# PFOP.net
KiCad netlist of a schematic drawn in EAGLE
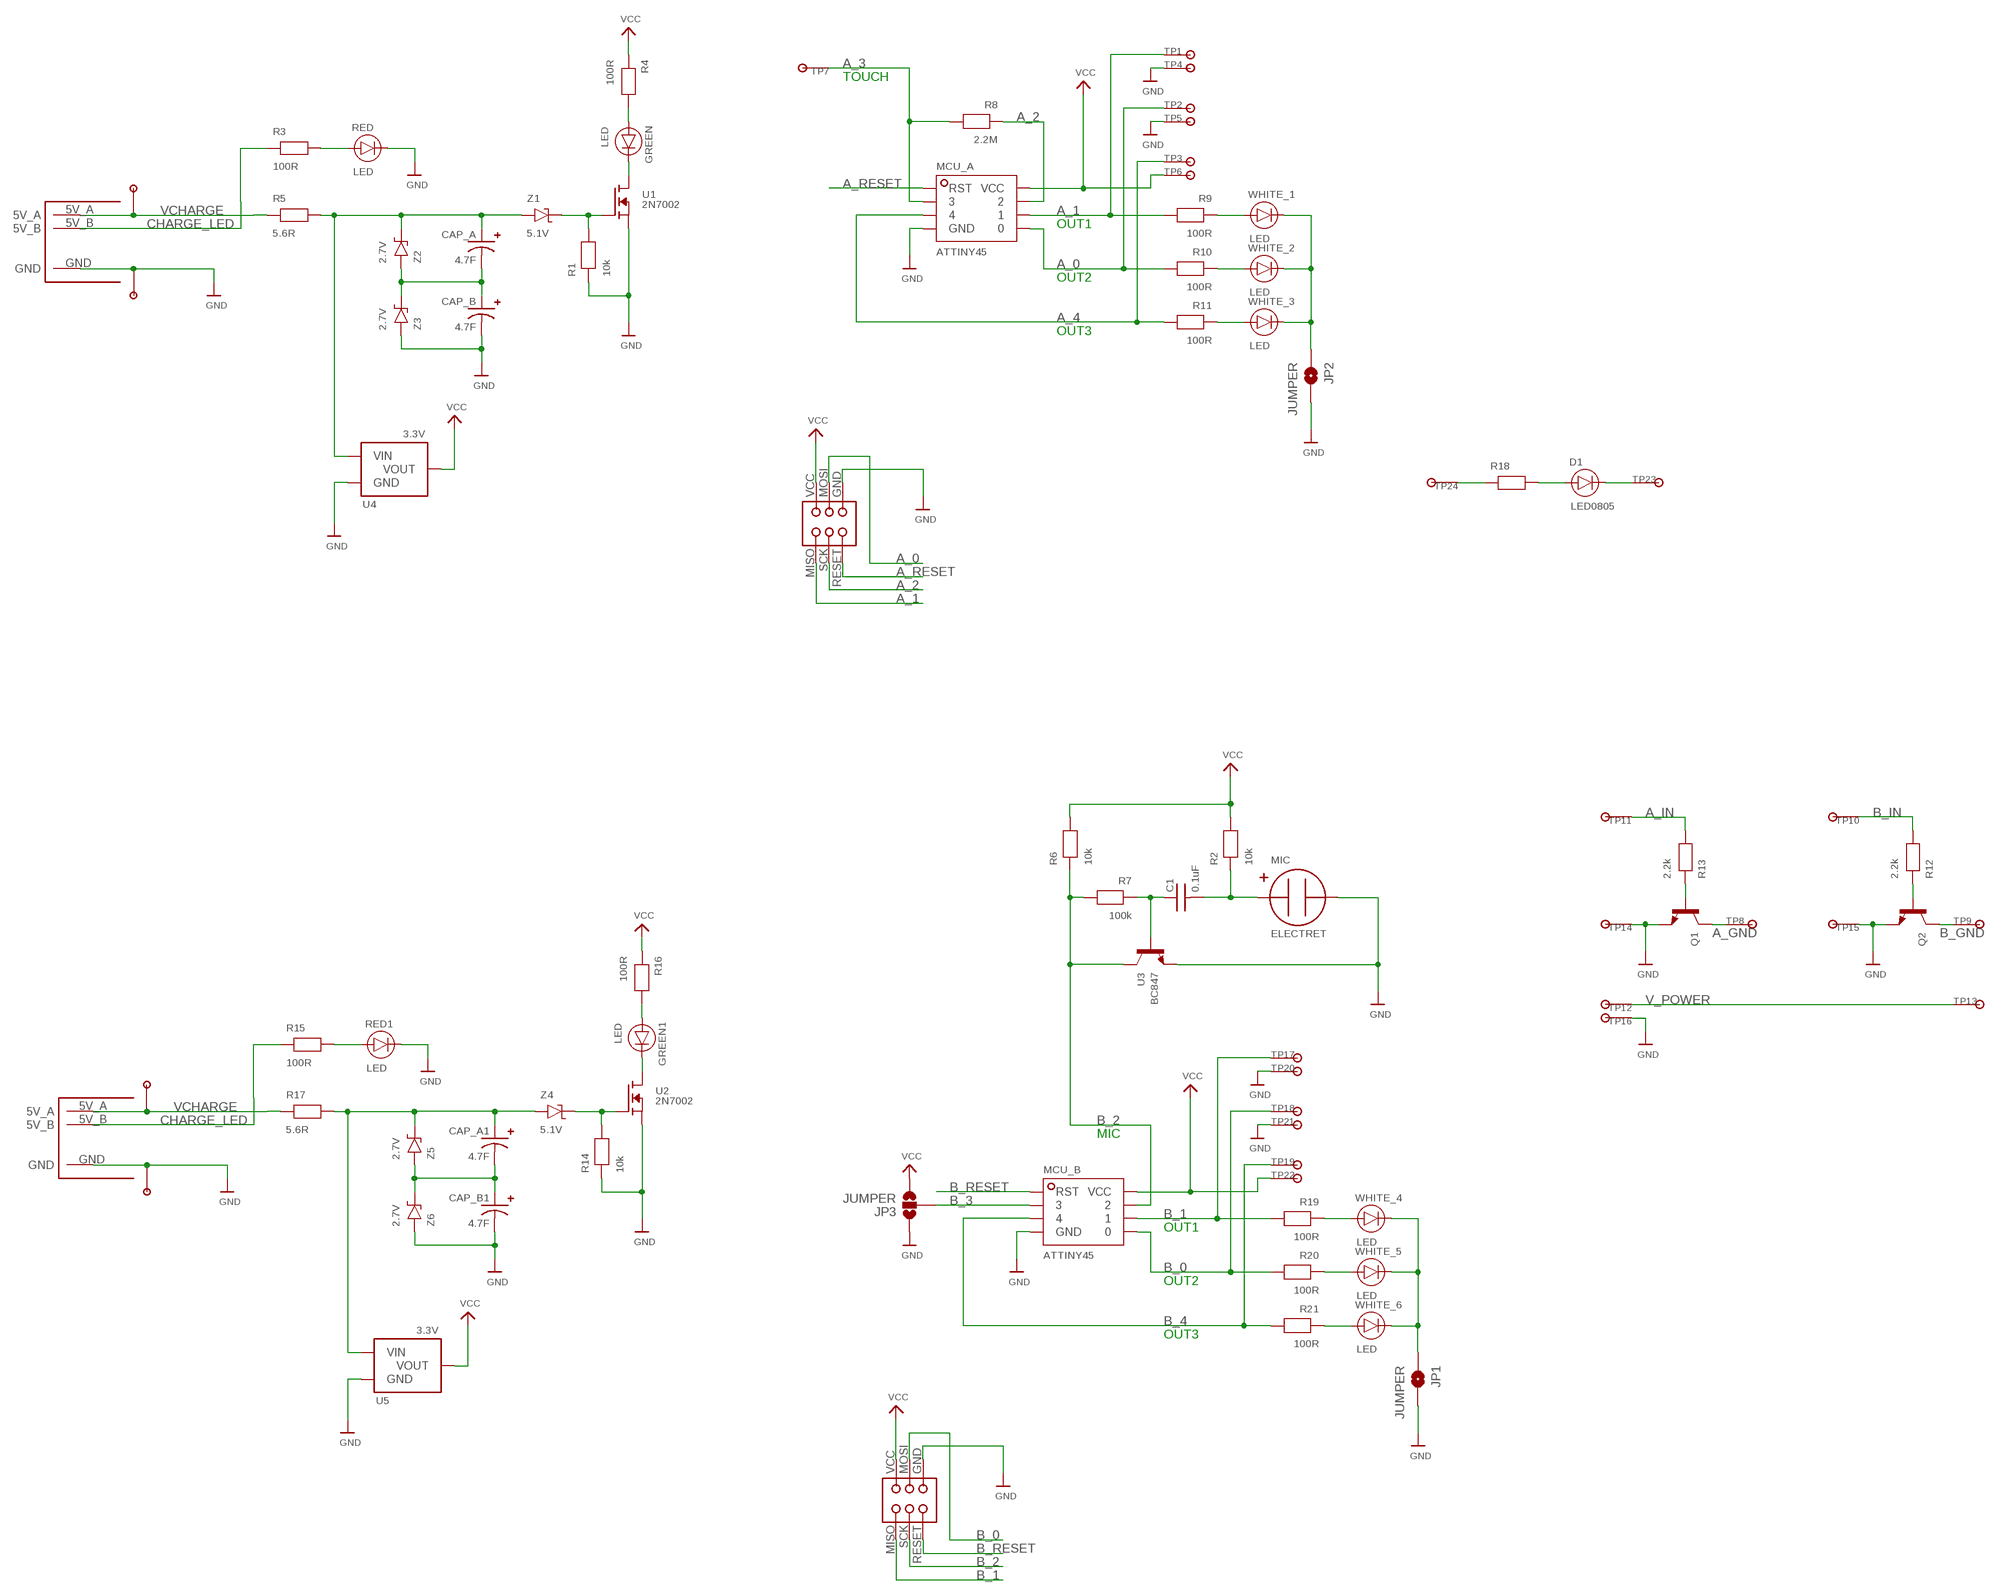
[diagram p0: schematic, sheet 1]

(export (version "E")
  (design (tool "Eeschema 10.0.6"))
  (components
    (comp (ref "C1")
      (value "0.1uF")
      (footprint "eagle-import:0805")
      (libsource (lib "eagle-import") (part "CAP"))
    )
    (comp (ref "CAP_A")
      (value "4.7F")
      (footprint "eagle-import:SUPERCAP_2.7V-4.7F")
      (libsource (lib "eagle-import") (part "SUPERCAP"))
    )
    (comp (ref "CAP_A1")
      (value "4.7F")
      (footprint "eagle-import:SUPERCAP_2.7V-4.7F")
      (libsource (lib "eagle-import") (part "SUPERCAP"))
    )
    (comp (ref "CAP_B")
      (value "4.7F")
      (footprint "eagle-import:SUPERCAP_2.7V-4.7F")
      (libsource (lib "eagle-import") (part "SUPERCAP"))
    )
    (comp (ref "CAP_B1")
      (value "4.7F")
      (footprint "eagle-import:SUPERCAP_2.7V-4.7F")
      (libsource (lib "eagle-import") (part "SUPERCAP"))
    )
    (comp (ref "D1")
      (value "LED0805")
      (footprint "eagle-import:0805_LED")
      (libsource (lib "eagle-import") (part "LED0805"))
    )
    (comp (ref "GREEN")
      (value "LED")
      (footprint "eagle-import:0805_LED")
      (libsource (lib "eagle-import") (part "LED0805"))
    )
    (comp (ref "GREEN1")
      (value "LED")
      (footprint "eagle-import:0805_LED")
      (libsource (lib "eagle-import") (part "LED0805"))
    )
    (comp (ref "J1")
      (value "ISP_HEADER")
      (footprint "eagle-import:ISP_HEADER")
      (libsource (lib "eagle-import") (part "ISP_HEADER"))
    )
    (comp (ref "J2")
      (value "ISP_HEADER")
      (footprint "eagle-import:ISP_HEADER")
      (libsource (lib "eagle-import") (part "ISP_HEADER"))
    )
    (comp (ref "JP1")
      (value "JUMPER")
      (footprint "eagle-import:SMT-JUMPER_2_NO_NO-SILK")
      (libsource (lib "eagle-import") (part "JUMPER-SMT_2_NO_NO-SILK"))
    )
    (comp (ref "JP2")
      (value "JUMPER")
      (footprint "eagle-import:SMT-JUMPER_2_NO_NO-SILK")
      (libsource (lib "eagle-import") (part "JUMPER-SMT_2_NO_NO-SILK"))
    )
    (comp (ref "JP3")
      (value "JUMPER")
      (footprint "eagle-import:SMT-JUMPER_3_NO_NO-SILK")
      (libsource (lib "eagle-import") (part "JUMPER-SMT_3_NO_NO-SILK"))
    )
    (comp (ref "MCU_A")
      (value "ATTINY45")
      (footprint "eagle-import:TSSOP-8")
      (libsource (lib "eagle-import") (part "ATTINY45"))
    )
    (comp (ref "MCU_B")
      (value "ATTINY45")
      (footprint "eagle-import:TSSOP-8")
      (libsource (lib "eagle-import") (part "ATTINY45"))
    )
    (comp (ref "MIC")
      (value "ELECTRET")
      (footprint "eagle-import:ELECTRET_4.5MM")
      (libsource (lib "eagle-import") (part "ELECTRET"))
    )
    (comp (ref "Q1")
      (value "POWER_TRANSISTOR")
      (footprint "eagle-import:POWER_TRANSISTOR")
      (libsource (lib "eagle-import") (part "POWER_TRANSISTOR"))
    )
    (comp (ref "Q2")
      (value "POWER_TRANSISTOR")
      (footprint "eagle-import:POWER_TRANSISTOR")
      (libsource (lib "eagle-import") (part "POWER_TRANSISTOR"))
    )
    (comp (ref "R1")
      (value "10k")
      (footprint "eagle-import:0805")
      (libsource (lib "eagle-import") (part "RESISTOR"))
    )
    (comp (ref "R2")
      (value "10k")
      (footprint "eagle-import:0805")
      (libsource (lib "eagle-import") (part "RESISTOR"))
    )
    (comp (ref "R3")
      (value "100R")
      (footprint "eagle-import:0805")
      (libsource (lib "eagle-import") (part "RESISTOR"))
    )
    (comp (ref "R4")
      (value "100R")
      (footprint "eagle-import:0805")
      (libsource (lib "eagle-import") (part "RESISTOR"))
    )
    (comp (ref "R5")
      (value "5.6R")
      (footprint "eagle-import:2512")
      (libsource (lib "eagle-import") (part "RESISTORPOWER"))
    )
    (comp (ref "R6")
      (value "10k")
      (footprint "eagle-import:0805")
      (libsource (lib "eagle-import") (part "RESISTOR"))
    )
    (comp (ref "R7")
      (value "100k")
      (footprint "eagle-import:0805")
      (libsource (lib "eagle-import") (part "RESISTOR"))
    )
    (comp (ref "R8")
      (value "2.2M")
      (footprint "eagle-import:0805")
      (libsource (lib "eagle-import") (part "RESISTOR"))
    )
    (comp (ref "R9")
      (value "100R")
      (footprint "eagle-import:0805")
      (libsource (lib "eagle-import") (part "RESISTOR"))
    )
    (comp (ref "R10")
      (value "100R")
      (footprint "eagle-import:0805")
      (libsource (lib "eagle-import") (part "RESISTOR"))
    )
    (comp (ref "R11")
      (value "100R")
      (footprint "eagle-import:0805")
      (libsource (lib "eagle-import") (part "RESISTOR"))
    )
    (comp (ref "R12")
      (value "2.2k")
      (footprint "eagle-import:0805")
      (libsource (lib "eagle-import") (part "RESISTOR"))
    )
    (comp (ref "R13")
      (value "2.2k")
      (footprint "eagle-import:0805")
      (libsource (lib "eagle-import") (part "RESISTOR"))
    )
    (comp (ref "R14")
      (value "10k")
      (footprint "eagle-import:0805")
      (libsource (lib "eagle-import") (part "RESISTOR"))
    )
    (comp (ref "R15")
      (value "100R")
      (footprint "eagle-import:0805")
      (libsource (lib "eagle-import") (part "RESISTOR"))
    )
    (comp (ref "R16")
      (value "100R")
      (footprint "eagle-import:0805")
      (libsource (lib "eagle-import") (part "RESISTOR"))
    )
    (comp (ref "R17")
      (value "5.6R")
      (footprint "eagle-import:2512")
      (libsource (lib "eagle-import") (part "RESISTORPOWER"))
    )
    (comp (ref "R18")
      (value "RESISTOR")
      (footprint "eagle-import:0805")
      (libsource (lib "eagle-import") (part "RESISTOR"))
    )
    (comp (ref "R19")
      (value "100R")
      (footprint "eagle-import:0805")
      (libsource (lib "eagle-import") (part "RESISTOR"))
    )
    (comp (ref "R20")
      (value "100R")
      (footprint "eagle-import:0805")
      (libsource (lib "eagle-import") (part "RESISTOR"))
    )
    (comp (ref "R21")
      (value "100R")
      (footprint "eagle-import:0805")
      (libsource (lib "eagle-import") (part "RESISTOR"))
    )
    (comp (ref "RED")
      (value "LED")
      (footprint "eagle-import:0805_LED")
      (libsource (lib "eagle-import") (part "LED0805"))
    )
    (comp (ref "RED1")
      (value "LED")
      (footprint "eagle-import:0805_LED")
      (libsource (lib "eagle-import") (part "LED0805"))
    )
    (comp (ref "TP1")
      (value "SEWTAPBIG")
      (footprint "eagle-import:BIGTAP")
      (libsource (lib "eagle-import") (part "SEWTAPBIG"))
    )
    (comp (ref "TP2")
      (value "SEWTAPBIG")
      (footprint "eagle-import:BIGTAP")
      (libsource (lib "eagle-import") (part "SEWTAPBIG"))
    )
    (comp (ref "TP3")
      (value "SEWTAPBIG")
      (footprint "eagle-import:BIGTAP")
      (libsource (lib "eagle-import") (part "SEWTAPBIG"))
    )
    (comp (ref "TP4")
      (value "SEWTAPBIG")
      (footprint "eagle-import:BIGTAP")
      (libsource (lib "eagle-import") (part "SEWTAPBIG"))
    )
    (comp (ref "TP5")
      (value "SEWTAPBIG")
      (footprint "eagle-import:BIGTAP")
      (libsource (lib "eagle-import") (part "SEWTAPBIG"))
    )
    (comp (ref "TP6")
      (value "SEWTAPBIG")
      (footprint "eagle-import:BIGTAP")
      (libsource (lib "eagle-import") (part "SEWTAPBIG"))
    )
    (comp (ref "TP7")
      (value "SEWTAP")
      (footprint "eagle-import:BIGTAP_TOUCH")
      (libsource (lib "eagle-import") (part "SEWTAP"))
    )
    (comp (ref "TP8")
      (value "SEWTAPBIG")
      (footprint "eagle-import:BIGTAP")
      (libsource (lib "eagle-import") (part "SEWTAPBIG"))
    )
    (comp (ref "TP9")
      (value "SEWTAPBIG")
      (footprint "eagle-import:BIGTAP")
      (libsource (lib "eagle-import") (part "SEWTAPBIG"))
    )
    (comp (ref "TP10")
      (value "SEWTAPBIG")
      (footprint "eagle-import:BIGTAP")
      (libsource (lib "eagle-import") (part "SEWTAPBIG"))
    )
    (comp (ref "TP11")
      (value "SEWTAPBIG")
      (footprint "eagle-import:BIGTAP")
      (libsource (lib "eagle-import") (part "SEWTAPBIG"))
    )
    (comp (ref "TP12")
      (value "SEWTAPBIG")
      (footprint "eagle-import:BIGTAP")
      (libsource (lib "eagle-import") (part "SEWTAPBIG"))
    )
    (comp (ref "TP13")
      (value "SEWTAPBIG")
      (footprint "eagle-import:BIGTAP")
      (libsource (lib "eagle-import") (part "SEWTAPBIG"))
    )
    (comp (ref "TP14")
      (value "SEWTAPBIG")
      (footprint "eagle-import:BIGTAP")
      (libsource (lib "eagle-import") (part "SEWTAPBIG"))
    )
    (comp (ref "TP15")
      (value "SEWTAPBIG")
      (footprint "eagle-import:BIGTAP")
      (libsource (lib "eagle-import") (part "SEWTAPBIG"))
    )
    (comp (ref "TP16")
      (value "SEWTAPBIG")
      (footprint "eagle-import:BIGTAP")
      (libsource (lib "eagle-import") (part "SEWTAPBIG"))
    )
    (comp (ref "TP17")
      (value "SEWTAPBIG")
      (footprint "eagle-import:BIGTAP")
      (libsource (lib "eagle-import") (part "SEWTAPBIG"))
    )
    (comp (ref "TP18")
      (value "SEWTAPBIG")
      (footprint "eagle-import:BIGTAP")
      (libsource (lib "eagle-import") (part "SEWTAPBIG"))
    )
    (comp (ref "TP19")
      (value "SEWTAPBIG")
      (footprint "eagle-import:BIGTAP")
      (libsource (lib "eagle-import") (part "SEWTAPBIG"))
    )
    (comp (ref "TP20")
      (value "SEWTAPBIG")
      (footprint "eagle-import:BIGTAP")
      (libsource (lib "eagle-import") (part "SEWTAPBIG"))
    )
    (comp (ref "TP21")
      (value "SEWTAPBIG")
      (footprint "eagle-import:BIGTAP")
      (libsource (lib "eagle-import") (part "SEWTAPBIG"))
    )
    (comp (ref "TP22")
      (value "SEWTAPBIG")
      (footprint "eagle-import:BIGTAP")
      (libsource (lib "eagle-import") (part "SEWTAPBIG"))
    )
    (comp (ref "TP23")
      (value "SEWTAPSEQUIN")
      (footprint "eagle-import:SEQUIN_TERMINAL")
      (libsource (lib "eagle-import") (part "SEWTAPSEQUIN"))
    )
    (comp (ref "TP24")
      (value "SEWTAPSEQUIN")
      (footprint "eagle-import:SEQUIN_TERMINAL")
      (libsource (lib "eagle-import") (part "SEWTAPSEQUIN"))
    )
    (comp (ref "U$1")
      (value "USB_CONN_POWER")
      (footprint "eagle-import:USB_CONN_POWER")
      (libsource (lib "eagle-import") (part "USB_CONN_POWER"))
    )
    (comp (ref "U$2")
      (value "1PIN")
      (footprint "eagle-import:1PIN")
      (libsource (lib "eagle-import") (part "1PIN"))
    )
    (comp (ref "U$3")
      (value "1PIN")
      (footprint "eagle-import:1PIN")
      (libsource (lib "eagle-import") (part "1PIN"))
    )
    (comp (ref "U$4")
      (value "USB_CONN_POWER")
      (footprint "eagle-import:USB_CONN_POWER")
      (libsource (lib "eagle-import") (part "USB_CONN_POWER"))
    )
    (comp (ref "U$5")
      (value "1PIN")
      (footprint "eagle-import:1PIN")
      (libsource (lib "eagle-import") (part "1PIN"))
    )
    (comp (ref "U$6")
      (value "1PIN")
      (footprint "eagle-import:1PIN")
      (libsource (lib "eagle-import") (part "1PIN"))
    )
    (comp (ref "U1")
      (value "2N7002")
      (footprint "eagle-import:SOT23")
      (libsource (lib "eagle-import") (part "2N7002"))
    )
    (comp (ref "U2")
      (value "2N7002")
      (footprint "eagle-import:SOT23")
      (libsource (lib "eagle-import") (part "2N7002"))
    )
    (comp (ref "U3")
      (value "BC847")
      (footprint "eagle-import:SOT23")
      (libsource (lib "eagle-import") (part "BC847"))
    )
    (comp (ref "U4")
      (value "3.3V")
      (footprint "eagle-import:SOT23")
      (libsource (lib "eagle-import") (part "LDO_REGULATOR"))
    )
    (comp (ref "U5")
      (value "3.3V")
      (footprint "eagle-import:SOT23")
      (libsource (lib "eagle-import") (part "LDO_REGULATOR"))
    )
    (comp (ref "WHITE_1")
      (value "LED")
      (footprint "eagle-import:PLCC-2_LED")
      (libsource (lib "eagle-import") (part "LEDPLCC-2"))
    )
    (comp (ref "WHITE_2")
      (value "LED")
      (footprint "eagle-import:PLCC-2_LED")
      (libsource (lib "eagle-import") (part "LEDPLCC-2"))
    )
    (comp (ref "WHITE_3")
      (value "LED")
      (footprint "eagle-import:PLCC-2_LED")
      (libsource (lib "eagle-import") (part "LEDPLCC-2"))
    )
    (comp (ref "WHITE_4")
      (value "LED")
      (footprint "eagle-import:PLCC-2_LED")
      (libsource (lib "eagle-import") (part "LEDPLCC-2"))
    )
    (comp (ref "WHITE_5")
      (value "LED")
      (footprint "eagle-import:PLCC-2_LED")
      (libsource (lib "eagle-import") (part "LEDPLCC-2"))
    )
    (comp (ref "WHITE_6")
      (value "LED")
      (footprint "eagle-import:PLCC-2_LED")
      (libsource (lib "eagle-import") (part "LEDPLCC-2"))
    )
    (comp (ref "Z1")
      (value "5.1V")
      (footprint "eagle-import:MINIMELF")
      (libsource (lib "eagle-import") (part "ZENER"))
    )
    (comp (ref "Z2")
      (value "2.7V")
      (footprint "eagle-import:MINIMELF")
      (libsource (lib "eagle-import") (part "ZENER"))
    )
    (comp (ref "Z3")
      (value "2.7V")
      (footprint "eagle-import:MINIMELF")
      (libsource (lib "eagle-import") (part "ZENER"))
    )
    (comp (ref "Z4")
      (value "5.1V")
      (footprint "eagle-import:MINIMELF")
      (libsource (lib "eagle-import") (part "ZENER"))
    )
    (comp (ref "Z5")
      (value "2.7V")
      (footprint "eagle-import:MINIMELF")
      (libsource (lib "eagle-import") (part "ZENER"))
    )
    (comp (ref "Z6")
      (value "2.7V")
      (footprint "eagle-import:MINIMELF")
      (libsource (lib "eagle-import") (part "ZENER"))
    )
  )
  (nets
    (net (code "1") (name "/A_0") (class "Default")
      (node (ref "J1") (pin "MOSI") (pinfunction "MOSI_MOSI") (pintype "bidirectional"))
      (node (ref "MCU_A") (pin "5") (pinfunction "0_5") (pintype "bidirectional"))
      (node (ref "R10") (pin "2") (pinfunction "P$2_2") (pintype "bidirectional"))
      (node (ref "TP2") (pin "P$1") (pinfunction "SEW_P$1") (pintype "bidirectional"))
    )
    (net (code "2") (name "/A_1") (class "Default")
      (node (ref "J1") (pin "MISO") (pinfunction "MISO_MISO") (pintype "bidirectional"))
      (node (ref "MCU_A") (pin "6") (pinfunction "1_6") (pintype "bidirectional"))
      (node (ref "R9") (pin "2") (pinfunction "P$2_2") (pintype "bidirectional"))
      (node (ref "TP1") (pin "P$1") (pinfunction "SEW_P$1") (pintype "bidirectional"))
    )
    (net (code "3") (name "/A_2") (class "Default")
      (node (ref "J1") (pin "SCK") (pinfunction "SCK_SCK") (pintype "bidirectional"))
      (node (ref "MCU_A") (pin "7") (pinfunction "2_7") (pintype "bidirectional"))
      (node (ref "R8") (pin "1") (pinfunction "P$1_1") (pintype "bidirectional"))
    )
    (net (code "4") (name "/A_3") (class "Default")
      (node (ref "MCU_A") (pin "2") (pinfunction "3_2") (pintype "bidirectional"))
      (node (ref "R8") (pin "2") (pinfunction "P$2_2") (pintype "bidirectional"))
      (node (ref "TP7") (pin "P$1") (pinfunction "SEW_P$1") (pintype "bidirectional"))
    )
    (net (code "5") (name "/A_4") (class "Default")
      (node (ref "MCU_A") (pin "3") (pinfunction "4_3") (pintype "bidirectional"))
      (node (ref "R11") (pin "2") (pinfunction "P$2_2") (pintype "bidirectional"))
      (node (ref "TP3") (pin "P$1") (pinfunction "SEW_P$1") (pintype "bidirectional"))
    )
    (net (code "6") (name "/A_GND") (class "Default")
      (node (ref "Q1") (pin "C") (pinfunction "C_C") (pintype "passive"))
      (node (ref "TP8") (pin "P$1") (pinfunction "SEW_P$1") (pintype "bidirectional"))
    )
    (net (code "7") (name "/A_IN") (class "Default")
      (node (ref "R13") (pin "2") (pinfunction "P$2_2") (pintype "bidirectional"))
      (node (ref "TP11") (pin "P$1") (pinfunction "SEW_P$1") (pintype "bidirectional"))
    )
    (net (code "8") (name "/A_RESET") (class "Default")
      (node (ref "J1") (pin "RESET") (pinfunction "RESET_RESET") (pintype "bidirectional"))
      (node (ref "MCU_A") (pin "1") (pinfunction "RST_1") (pintype "bidirectional"))
    )
    (net (code "9") (name "/B_0") (class "Default")
      (node (ref "J2") (pin "MOSI") (pinfunction "MOSI_MOSI") (pintype "bidirectional"))
      (node (ref "MCU_B") (pin "5") (pinfunction "0_5") (pintype "bidirectional"))
      (node (ref "R20") (pin "2") (pinfunction "P$2_2") (pintype "bidirectional"))
      (node (ref "TP18") (pin "P$1") (pinfunction "SEW_P$1") (pintype "bidirectional"))
    )
    (net (code "10") (name "/B_1") (class "Default")
      (node (ref "J2") (pin "MISO") (pinfunction "MISO_MISO") (pintype "bidirectional"))
      (node (ref "MCU_B") (pin "6") (pinfunction "1_6") (pintype "bidirectional"))
      (node (ref "R19") (pin "2") (pinfunction "P$2_2") (pintype "bidirectional"))
      (node (ref "TP17") (pin "P$1") (pinfunction "SEW_P$1") (pintype "bidirectional"))
    )
    (net (code "11") (name "/B_2") (class "Default")
      (node (ref "J2") (pin "SCK") (pinfunction "SCK_SCK") (pintype "bidirectional"))
      (node (ref "MCU_B") (pin "7") (pinfunction "2_7") (pintype "bidirectional"))
      (node (ref "R6") (pin "1") (pinfunction "P$1_1") (pintype "bidirectional"))
      (node (ref "R7") (pin "2") (pinfunction "P$2_2") (pintype "bidirectional"))
      (node (ref "U3") (pin "3") (pinfunction "C_3") (pintype "passive"))
    )
    (net (code "12") (name "/B_3") (class "Default")
      (node (ref "JP3") (pin "2") (pinfunction "2_2") (pintype "passive"))
      (node (ref "MCU_B") (pin "2") (pinfunction "3_2") (pintype "bidirectional"))
    )
    (net (code "13") (name "/B_4") (class "Default")
      (node (ref "MCU_B") (pin "3") (pinfunction "4_3") (pintype "bidirectional"))
      (node (ref "R21") (pin "2") (pinfunction "P$2_2") (pintype "bidirectional"))
      (node (ref "TP19") (pin "P$1") (pinfunction "SEW_P$1") (pintype "bidirectional"))
    )
    (net (code "14") (name "/B_GND") (class "Default")
      (node (ref "Q2") (pin "C") (pinfunction "C_C") (pintype "passive"))
      (node (ref "TP9") (pin "P$1") (pinfunction "SEW_P$1") (pintype "bidirectional"))
    )
    (net (code "15") (name "/B_IN") (class "Default")
      (node (ref "R12") (pin "2") (pinfunction "P$2_2") (pintype "bidirectional"))
      (node (ref "TP10") (pin "P$1") (pinfunction "SEW_P$1") (pintype "bidirectional"))
    )
    (net (code "16") (name "/B_RESET") (class "Default")
      (node (ref "J2") (pin "RESET") (pinfunction "RESET_RESET") (pintype "bidirectional"))
      (node (ref "MCU_B") (pin "1") (pinfunction "RST_1") (pintype "bidirectional"))
    )
    (net (code "17") (name "/CHARGE_LED") (class "Default")
      (node (ref "R15") (pin "1") (pinfunction "P$1_1") (pintype "bidirectional"))
      (node (ref "R3") (pin "1") (pinfunction "P$1_1") (pintype "bidirectional"))
      (node (ref "U$1") (pin "5V_B") (pinfunction "5V_B_5V_B") (pintype "bidirectional"))
      (node (ref "U$4") (pin "5V_B") (pinfunction "5V_B_5V_B") (pintype "bidirectional"))
    )
    (net (code "18") (name "/VCHARGE") (class "Default")
      (node (ref "R17") (pin "1") (pinfunction "P$1_1") (pintype "bidirectional"))
      (node (ref "R5") (pin "1") (pinfunction "P$1_1") (pintype "bidirectional"))
      (node (ref "U$1") (pin "5V_A") (pinfunction "5V_A_5V_A") (pintype "bidirectional"))
      (node (ref "U$2") (pin "P$1") (pinfunction "P$1_P$1") (pintype "bidirectional"))
      (node (ref "U$4") (pin "5V_A") (pinfunction "5V_A_5V_A") (pintype "bidirectional"))
      (node (ref "U$5") (pin "P$1") (pinfunction "P$1_P$1") (pintype "bidirectional"))
    )
    (net (code "19") (name "/V_POWER") (class "Default")
      (node (ref "TP12") (pin "P$1") (pinfunction "SEW_P$1") (pintype "bidirectional"))
      (node (ref "TP13") (pin "P$1") (pinfunction "SEW_P$1") (pintype "bidirectional"))
    )
    (net (code "20") (name "GND") (class "Default")
      (node (ref "CAP_B") (pin "-") (pinfunction "-_-") (pintype "passive"))
      (node (ref "CAP_B1") (pin "-") (pinfunction "-_-") (pintype "passive"))
      (node (ref "J1") (pin "GND") (pinfunction "GND_GND") (pintype "bidirectional"))
      (node (ref "J2") (pin "GND") (pinfunction "GND_GND") (pintype "bidirectional"))
      (node (ref "JP1") (pin "2") (pinfunction "2_2") (pintype "passive"))
      (node (ref "JP2") (pin "2") (pinfunction "2_2") (pintype "passive"))
      (node (ref "JP3") (pin "1") (pinfunction "1_1") (pintype "passive"))
      (node (ref "MCU_A") (pin "4") (pinfunction "GND_4") (pintype "bidirectional"))
      (node (ref "MCU_B") (pin "4") (pinfunction "GND_4") (pintype "bidirectional"))
      (node (ref "MIC") (pin "-") (pinfunction "V-_-") (pintype "bidirectional"))
      (node (ref "Q1") (pin "E") (pinfunction "E_E") (pintype "passive"))
      (node (ref "Q2") (pin "E") (pinfunction "E_E") (pintype "passive"))
      (node (ref "R1") (pin "1") (pinfunction "P$1_1") (pintype "bidirectional"))
      (node (ref "R14") (pin "1") (pinfunction "P$1_1") (pintype "bidirectional"))
      (node (ref "RED") (pin "-") (pinfunction "-_-") (pintype "bidirectional"))
      (node (ref "RED1") (pin "-") (pinfunction "-_-") (pintype "bidirectional"))
      (node (ref "TP14") (pin "P$1") (pinfunction "SEW_P$1") (pintype "bidirectional"))
      (node (ref "TP15") (pin "P$1") (pinfunction "SEW_P$1") (pintype "bidirectional"))
      (node (ref "TP16") (pin "P$1") (pinfunction "SEW_P$1") (pintype "bidirectional"))
      (node (ref "TP20") (pin "P$1") (pinfunction "SEW_P$1") (pintype "bidirectional"))
      (node (ref "TP21") (pin "P$1") (pinfunction "SEW_P$1") (pintype "bidirectional"))
      (node (ref "TP4") (pin "P$1") (pinfunction "SEW_P$1") (pintype "bidirectional"))
      (node (ref "TP5") (pin "P$1") (pinfunction "SEW_P$1") (pintype "bidirectional"))
      (node (ref "U$1") (pin "GND") (pinfunction "GND_GND") (pintype "bidirectional"))
      (node (ref "U$3") (pin "P$1") (pinfunction "P$1_P$1") (pintype "bidirectional"))
      (node (ref "U$4") (pin "GND") (pinfunction "GND_GND") (pintype "bidirectional"))
      (node (ref "U$6") (pin "P$1") (pinfunction "P$1_P$1") (pintype "bidirectional"))
      (node (ref "U1") (pin "2") (pinfunction "S_2") (pintype "bidirectional"))
      (node (ref "U2") (pin "2") (pinfunction "S_2") (pintype "bidirectional"))
      (node (ref "U3") (pin "2") (pinfunction "E_2") (pintype "passive"))
      (node (ref "U4") (pin "1") (pinfunction "GND_1") (pintype "bidirectional"))
      (node (ref "U5") (pin "1") (pinfunction "GND_1") (pintype "bidirectional"))
      (node (ref "Z3") (pin "1") (pinfunction "P$1_1") (pintype "bidirectional"))
      (node (ref "Z6") (pin "1") (pinfunction "P$1_1") (pintype "bidirectional"))
    )
    (net (code "21") (name "Net-(JP1-Pad1)") (class "Default")
      (node (ref "JP1") (pin "1") (pinfunction "1_1") (pintype "passive"))
      (node (ref "WHITE_4") (pin "-") (pinfunction "-_-") (pintype "bidirectional"))
      (node (ref "WHITE_5") (pin "-") (pinfunction "-_-") (pintype "bidirectional"))
      (node (ref "WHITE_6") (pin "-") (pinfunction "-_-") (pintype "bidirectional"))
    )
    (net (code "22") (name "Net-(JP2-Pad1)") (class "Default")
      (node (ref "JP2") (pin "1") (pinfunction "1_1") (pintype "passive"))
      (node (ref "WHITE_1") (pin "-") (pinfunction "-_-") (pintype "bidirectional"))
      (node (ref "WHITE_2") (pin "-") (pinfunction "-_-") (pintype "bidirectional"))
      (node (ref "WHITE_3") (pin "-") (pinfunction "-_-") (pintype "bidirectional"))
    )
    (net (code "23") (name "Net-(MIC-V+)") (class "Default")
      (node (ref "C1") (pin "2") (pinfunction "2_2") (pintype "passive"))
      (node (ref "MIC") (pin "+") (pinfunction "V+_+") (pintype "bidirectional"))
      (node (ref "R2") (pin "1") (pinfunction "P$1_1") (pintype "bidirectional"))
    )
    (net (code "24") (name "Net-(R1-P$2)") (class "Default")
      (node (ref "R1") (pin "2") (pinfunction "P$2_2") (pintype "bidirectional"))
      (node (ref "U1") (pin "1") (pinfunction "G_1") (pintype "bidirectional"))
      (node (ref "Z1") (pin "2") (pinfunction "P$2_2") (pintype "bidirectional"))
    )
    (net (code "25") (name "Net-(R3-P$2)") (class "Default")
      (node (ref "R3") (pin "2") (pinfunction "P$2_2") (pintype "bidirectional"))
      (node (ref "RED") (pin "+") (pinfunction "+_+") (pintype "bidirectional"))
    )
    (net (code "26") (name "Net-(R4-P$2)") (class "Default")
      (node (ref "GREEN") (pin "+") (pinfunction "+_+") (pintype "bidirectional"))
      (node (ref "R4") (pin "2") (pinfunction "P$2_2") (pintype "bidirectional"))
    )
    (net (code "27") (name "Net-(R5-P$2)") (class "Default")
      (node (ref "CAP_A") (pin "+") (pinfunction "+_+") (pintype "passive"))
      (node (ref "R5") (pin "2") (pinfunction "P$2_2") (pintype "bidirectional"))
      (node (ref "U4") (pin "3") (pinfunction "VIN_3") (pintype "bidirectional"))
      (node (ref "Z1") (pin "1") (pinfunction "P$1_1") (pintype "bidirectional"))
      (node (ref "Z2") (pin "2") (pinfunction "P$2_2") (pintype "bidirectional"))
    )
    (net (code "28") (name "Net-(R7-P$1)") (class "Default")
      (node (ref "C1") (pin "1") (pinfunction "1_1") (pintype "passive"))
      (node (ref "R7") (pin "1") (pinfunction "P$1_1") (pintype "bidirectional"))
      (node (ref "U3") (pin "1") (pinfunction "B_1") (pintype "passive"))
    )
    (net (code "29") (name "Net-(R9-P$1)") (class "Default")
      (node (ref "R9") (pin "1") (pinfunction "P$1_1") (pintype "bidirectional"))
      (node (ref "WHITE_1") (pin "+") (pinfunction "+_+") (pintype "bidirectional"))
    )
    (net (code "30") (name "Net-(R10-P$1)") (class "Default")
      (node (ref "R10") (pin "1") (pinfunction "P$1_1") (pintype "bidirectional"))
      (node (ref "WHITE_2") (pin "+") (pinfunction "+_+") (pintype "bidirectional"))
    )
    (net (code "31") (name "Net-(R11-P$1)") (class "Default")
      (node (ref "R11") (pin "1") (pinfunction "P$1_1") (pintype "bidirectional"))
      (node (ref "WHITE_3") (pin "+") (pinfunction "+_+") (pintype "bidirectional"))
    )
    (net (code "32") (name "Net-(R12-P$1)") (class "Default")
      (node (ref "Q2") (pin "B") (pinfunction "B_B") (pintype "passive"))
      (node (ref "R12") (pin "1") (pinfunction "P$1_1") (pintype "bidirectional"))
    )
    (net (code "33") (name "Net-(R13-P$1)") (class "Default")
      (node (ref "Q1") (pin "B") (pinfunction "B_B") (pintype "passive"))
      (node (ref "R13") (pin "1") (pinfunction "P$1_1") (pintype "bidirectional"))
    )
    (net (code "34") (name "Net-(R14-P$2)") (class "Default")
      (node (ref "R14") (pin "2") (pinfunction "P$2_2") (pintype "bidirectional"))
      (node (ref "U2") (pin "1") (pinfunction "G_1") (pintype "bidirectional"))
      (node (ref "Z4") (pin "2") (pinfunction "P$2_2") (pintype "bidirectional"))
    )
    (net (code "35") (name "Net-(R15-P$2)") (class "Default")
      (node (ref "R15") (pin "2") (pinfunction "P$2_2") (pintype "bidirectional"))
      (node (ref "RED1") (pin "+") (pinfunction "+_+") (pintype "bidirectional"))
    )
    (net (code "36") (name "Net-(R16-P$2)") (class "Default")
      (node (ref "GREEN1") (pin "+") (pinfunction "+_+") (pintype "bidirectional"))
      (node (ref "R16") (pin "2") (pinfunction "P$2_2") (pintype "bidirectional"))
    )
    (net (code "37") (name "Net-(R17-P$2)") (class "Default")
      (node (ref "CAP_A1") (pin "+") (pinfunction "+_+") (pintype "passive"))
      (node (ref "R17") (pin "2") (pinfunction "P$2_2") (pintype "bidirectional"))
      (node (ref "U5") (pin "3") (pinfunction "VIN_3") (pintype "bidirectional"))
      (node (ref "Z4") (pin "1") (pinfunction "P$1_1") (pintype "bidirectional"))
      (node (ref "Z5") (pin "2") (pinfunction "P$2_2") (pintype "bidirectional"))
    )
    (net (code "38") (name "Net-(R18-P$1)") (class "Default")
      (node (ref "R18") (pin "1") (pinfunction "P$1_1") (pintype "bidirectional"))
      (node (ref "TP24") (pin "P$1") (pinfunction "SEW_P$1") (pintype "bidirectional"))
    )
    (net (code "39") (name "Net-(R18-P$2)") (class "Default")
      (node (ref "D1") (pin "+") (pinfunction "+_+") (pintype "bidirectional"))
      (node (ref "R18") (pin "2") (pinfunction "P$2_2") (pintype "bidirectional"))
    )
    (net (code "40") (name "Net-(R19-P$1)") (class "Default")
      (node (ref "R19") (pin "1") (pinfunction "P$1_1") (pintype "bidirectional"))
      (node (ref "WHITE_4") (pin "+") (pinfunction "+_+") (pintype "bidirectional"))
    )
    (net (code "41") (name "Net-(R20-P$1)") (class "Default")
      (node (ref "R20") (pin "1") (pinfunction "P$1_1") (pintype "bidirectional"))
      (node (ref "WHITE_5") (pin "+") (pinfunction "+_+") (pintype "bidirectional"))
    )
    (net (code "42") (name "Net-(R21-P$1)") (class "Default")
      (node (ref "R21") (pin "1") (pinfunction "P$1_1") (pintype "bidirectional"))
      (node (ref "WHITE_6") (pin "+") (pinfunction "+_+") (pintype "bidirectional"))
    )
    (net (code "43") (name "Net-(TP23-SEW)") (class "Default")
      (node (ref "D1") (pin "-") (pinfunction "-_-") (pintype "bidirectional"))
      (node (ref "TP23") (pin "P$1") (pinfunction "SEW_P$1") (pintype "bidirectional"))
    )
    (net (code "44") (name "Net-(U1-D)") (class "Default")
      (node (ref "GREEN") (pin "-") (pinfunction "-_-") (pintype "bidirectional"))
      (node (ref "U1") (pin "3") (pinfunction "D_3") (pintype "bidirectional"))
    )
    (net (code "45") (name "Net-(U2-D)") (class "Default")
      (node (ref "GREEN1") (pin "-") (pinfunction "-_-") (pintype "bidirectional"))
      (node (ref "U2") (pin "3") (pinfunction "D_3") (pintype "bidirectional"))
    )
    (net (code "46") (name "Net-(Z2-P$1)") (class "Default")
      (node (ref "CAP_A") (pin "-") (pinfunction "-_-") (pintype "passive"))
      (node (ref "CAP_B") (pin "+") (pinfunction "+_+") (pintype "passive"))
      (node (ref "Z2") (pin "1") (pinfunction "P$1_1") (pintype "bidirectional"))
      (node (ref "Z3") (pin "2") (pinfunction "P$2_2") (pintype "bidirectional"))
    )
    (net (code "47") (name "Net-(Z5-P$1)") (class "Default")
      (node (ref "CAP_A1") (pin "-") (pinfunction "-_-") (pintype "passive"))
      (node (ref "CAP_B1") (pin "+") (pinfunction "+_+") (pintype "passive"))
      (node (ref "Z5") (pin "1") (pinfunction "P$1_1") (pintype "bidirectional"))
      (node (ref "Z6") (pin "2") (pinfunction "P$2_2") (pintype "bidirectional"))
    )
    (net (code "48") (name "VCC") (class "Default")
      (node (ref "J1") (pin "VCC") (pinfunction "VCC_VCC") (pintype "bidirectional"))
      (node (ref "J2") (pin "VCC") (pinfunction "VCC_VCC") (pintype "bidirectional"))
      (node (ref "JP3") (pin "3") (pinfunction "3_3") (pintype "passive"))
      (node (ref "MCU_A") (pin "8") (pinfunction "VCC_8") (pintype "bidirectional"))
      (node (ref "MCU_B") (pin "8") (pinfunction "VCC_8") (pintype "bidirectional"))
      (node (ref "R16") (pin "1") (pinfunction "P$1_1") (pintype "bidirectional"))
      (node (ref "R2") (pin "2") (pinfunction "P$2_2") (pintype "bidirectional"))
      (node (ref "R4") (pin "1") (pinfunction "P$1_1") (pintype "bidirectional"))
      (node (ref "R6") (pin "2") (pinfunction "P$2_2") (pintype "bidirectional"))
      (node (ref "TP22") (pin "P$1") (pinfunction "SEW_P$1") (pintype "bidirectional"))
      (node (ref "TP6") (pin "P$1") (pinfunction "SEW_P$1") (pintype "bidirectional"))
      (node (ref "U4") (pin "2") (pinfunction "VOUT_2") (pintype "bidirectional"))
      (node (ref "U5") (pin "2") (pinfunction "VOUT_2") (pintype "bidirectional"))
    )
  )
)
